# OLD_Trigger_And_Clock_Muxing.net
KiCad netlist of a schematic drawn in Altium Designer
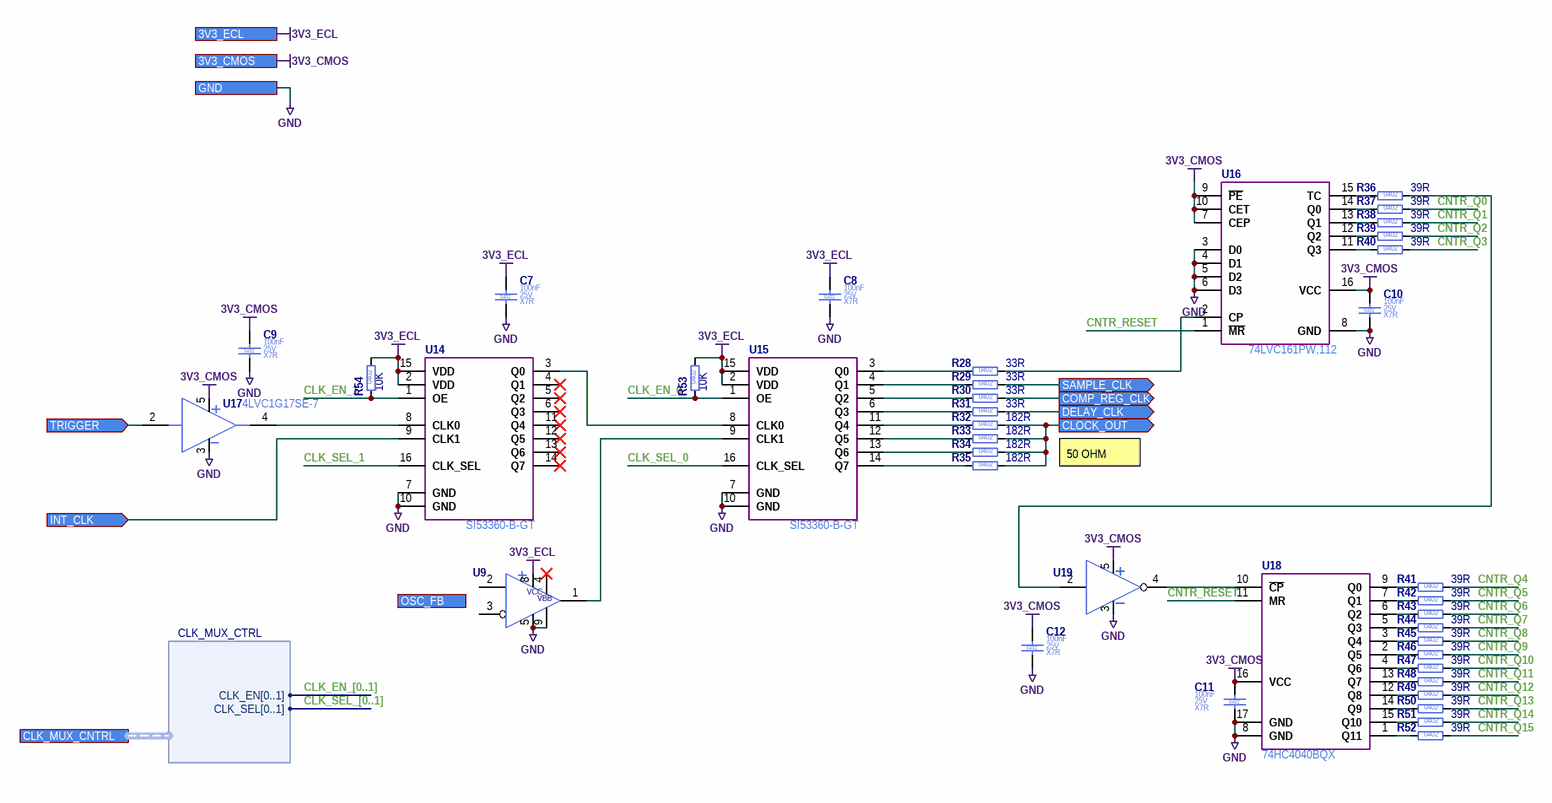
[diagram p0: OLD_Trigger_And_Clock_Muxing.SchDoc]

(export (version "E")
  (design (tool "Eeschema 10.0.6"))
  (components
    (comp (ref "C7")
      (value "C_100NF_25V_X7R_0402_10")
      (footprint "C_0402_1005")
      (description "Ceramic Capacitor")
      (fields
        (field (name "CASE/PACKAGE") "0402")
        (field (name "VOLTAGE RATING (DC)") "25V")
        (field (name "DIELECTRIC") "X7R")
        (field (name "CAPACITANCE") "100nF")
        (field (name "TOLERANCE") "10%")
        (field (name "MANUFACTURER PART NUMBER") "EMK105B7104KV-F")
      )
      (libsource (lib "7Sigma") (part "C"))
    )
    (comp (ref "C8")
      (value "C_100NF_25V_X7R_0402_10")
      (footprint "C_0402_1005")
      (description "Ceramic Capacitor")
      (fields
        (field (name "CASE/PACKAGE") "0402")
        (field (name "VOLTAGE RATING (DC)") "25V")
        (field (name "DIELECTRIC") "X7R")
        (field (name "CAPACITANCE") "100nF")
        (field (name "TOLERANCE") "10%")
        (field (name "MANUFACTURER PART NUMBER") "EMK105B7104KV-F")
      )
      (libsource (lib "7Sigma") (part "C"))
    )
    (comp (ref "C9")
      (value "C_100NF_25V_X7R_0402_10")
      (footprint "C_0402_1005")
      (description "Ceramic Capacitor")
      (fields
        (field (name "CASE/PACKAGE") "0402")
        (field (name "VOLTAGE RATING (DC)") "25V")
        (field (name "DIELECTRIC") "X7R")
        (field (name "CAPACITANCE") "100nF")
        (field (name "TOLERANCE") "10%")
        (field (name "MANUFACTURER PART NUMBER") "EMK105B7104KV-F")
      )
      (libsource (lib "7Sigma") (part "C"))
    )
    (comp (ref "C10")
      (value "C_100NF_25V_X7R_0402_10")
      (footprint "C_0402_1005")
      (description "Ceramic Capacitor")
      (fields
        (field (name "CASE/PACKAGE") "0402")
        (field (name "VOLTAGE RATING (DC)") "25V")
        (field (name "DIELECTRIC") "X7R")
        (field (name "CAPACITANCE") "100nF")
        (field (name "TOLERANCE") "10%")
        (field (name "MANUFACTURER PART NUMBER") "EMK105B7104KV-F")
      )
      (libsource (lib "7Sigma") (part "C"))
    )
    (comp (ref "C11")
      (value "C_100NF_25V_X7R_0402_10")
      (footprint "C_0402_1005")
      (description "Ceramic Capacitor")
      (fields
        (field (name "CASE/PACKAGE") "0402")
        (field (name "VOLTAGE RATING (DC)") "25V")
        (field (name "DIELECTRIC") "X7R")
        (field (name "CAPACITANCE") "100nF")
        (field (name "TOLERANCE") "10%")
        (field (name "MANUFACTURER PART NUMBER") "EMK105B7104KV-F")
      )
      (libsource (lib "7Sigma") (part "C"))
    )
    (comp (ref "C12")
      (value "C_100NF_25V_X7R_0402_10")
      (footprint "C_0402_1005")
      (description "Ceramic Capacitor")
      (fields
        (field (name "CASE/PACKAGE") "0402")
        (field (name "VOLTAGE RATING (DC)") "25V")
        (field (name "DIELECTRIC") "X7R")
        (field (name "CAPACITANCE") "100nF")
        (field (name "TOLERANCE") "10%")
        (field (name "MANUFACTURER PART NUMBER") "EMK105B7104KV-F")
      )
      (libsource (lib "7Sigma") (part "C"))
    )
    (comp (ref "R28")
      (value "R_33R_0402_1")
      (footprint "R_0402_1005")
      (description "Thick Film Resistor")
      (fields
        (field (name "RESISTANCE") "33R")
        (field (name "CASE/PACKAGE") "0402")
        (field (name "TOLERANCE") "1%")
        (field (name "MANUFACTURER") "Yageo")
      )
      (libsource (lib "7Sigma") (part "R"))
    )
    (comp (ref "R29")
      (value "R_33R_0402_1")
      (footprint "R_0402_1005")
      (description "Thick Film Resistor")
      (fields
        (field (name "RESISTANCE") "33R")
        (field (name "CASE/PACKAGE") "0402")
        (field (name "TOLERANCE") "1%")
        (field (name "MANUFACTURER") "Yageo")
      )
      (libsource (lib "7Sigma") (part "R"))
    )
    (comp (ref "R30")
      (value "R_33R_0402_1")
      (footprint "R_0402_1005")
      (description "Thick Film Resistor")
      (fields
        (field (name "RESISTANCE") "33R")
        (field (name "CASE/PACKAGE") "0402")
        (field (name "TOLERANCE") "1%")
        (field (name "MANUFACTURER") "Yageo")
      )
      (libsource (lib "7Sigma") (part "R"))
    )
    (comp (ref "R31")
      (value "R_33R_0402_1")
      (footprint "R_0402_1005")
      (description "Thick Film Resistor")
      (fields
        (field (name "RESISTANCE") "33R")
        (field (name "CASE/PACKAGE") "0402")
        (field (name "TOLERANCE") "1%")
        (field (name "MANUFACTURER") "Yageo")
      )
      (libsource (lib "7Sigma") (part "R"))
    )
    (comp (ref "R32")
      (value "R_182R_0402_1")
      (footprint "R_0402_1005")
      (description "Thick Film Resistor")
      (fields
        (field (name "RESISTANCE") "182R")
        (field (name "CASE/PACKAGE") "0402")
        (field (name "TOLERANCE") "1%")
        (field (name "MANUFACTURER") "Yageo")
      )
      (libsource (lib "7Sigma") (part "R"))
    )
    (comp (ref "R33")
      (value "R_182R_0402_1")
      (footprint "R_0402_1005")
      (description "Thick Film Resistor")
      (fields
        (field (name "RESISTANCE") "182R")
        (field (name "CASE/PACKAGE") "0402")
        (field (name "TOLERANCE") "1%")
        (field (name "MANUFACTURER") "Yageo")
      )
      (libsource (lib "7Sigma") (part "R"))
    )
    (comp (ref "R34")
      (value "R_182R_0402_1")
      (footprint "R_0402_1005")
      (description "Thick Film Resistor")
      (fields
        (field (name "RESISTANCE") "182R")
        (field (name "CASE/PACKAGE") "0402")
        (field (name "TOLERANCE") "1%")
        (field (name "MANUFACTURER") "Yageo")
      )
      (libsource (lib "7Sigma") (part "R"))
    )
    (comp (ref "R35")
      (value "R_182R_0402_1")
      (footprint "R_0402_1005")
      (description "Thick Film Resistor")
      (fields
        (field (name "RESISTANCE") "182R")
        (field (name "CASE/PACKAGE") "0402")
        (field (name "TOLERANCE") "1%")
        (field (name "MANUFACTURER") "Yageo")
      )
      (libsource (lib "7Sigma") (part "R"))
    )
    (comp (ref "R36")
      (value "R_39R_0402_1")
      (footprint "R_0402_1005")
      (description "Thick Film Resistor")
      (fields
        (field (name "RESISTANCE") "39R")
        (field (name "CASE/PACKAGE") "0402")
        (field (name "TOLERANCE") "1%")
        (field (name "MANUFACTURER") "Yageo")
      )
      (libsource (lib "7Sigma") (part "R"))
    )
    (comp (ref "R37")
      (value "R_39R_0402_1")
      (footprint "R_0402_1005")
      (description "Thick Film Resistor")
      (fields
        (field (name "RESISTANCE") "39R")
        (field (name "CASE/PACKAGE") "0402")
        (field (name "TOLERANCE") "1%")
        (field (name "MANUFACTURER") "Yageo")
      )
      (libsource (lib "7Sigma") (part "R"))
    )
    (comp (ref "R38")
      (value "R_39R_0402_1")
      (footprint "R_0402_1005")
      (description "Thick Film Resistor")
      (fields
        (field (name "RESISTANCE") "39R")
        (field (name "CASE/PACKAGE") "0402")
        (field (name "TOLERANCE") "1%")
        (field (name "MANUFACTURER") "Yageo")
      )
      (libsource (lib "7Sigma") (part "R"))
    )
    (comp (ref "R39")
      (value "R_39R_0402_1")
      (footprint "R_0402_1005")
      (description "Thick Film Resistor")
      (fields
        (field (name "RESISTANCE") "39R")
        (field (name "CASE/PACKAGE") "0402")
        (field (name "TOLERANCE") "1%")
        (field (name "MANUFACTURER") "Yageo")
      )
      (libsource (lib "7Sigma") (part "R"))
    )
    (comp (ref "R40")
      (value "R_39R_0402_1")
      (footprint "R_0402_1005")
      (description "Thick Film Resistor")
      (fields
        (field (name "RESISTANCE") "39R")
        (field (name "CASE/PACKAGE") "0402")
        (field (name "TOLERANCE") "1%")
        (field (name "MANUFACTURER") "Yageo")
      )
      (libsource (lib "7Sigma") (part "R"))
    )
    (comp (ref "R41")
      (value "R_39R_0402_1")
      (footprint "R_0402_1005")
      (description "Thick Film Resistor")
      (fields
        (field (name "RESISTANCE") "39R")
        (field (name "CASE/PACKAGE") "0402")
        (field (name "TOLERANCE") "1%")
        (field (name "MANUFACTURER") "Yageo")
      )
      (libsource (lib "7Sigma") (part "R"))
    )
    (comp (ref "R42")
      (value "R_39R_0402_1")
      (footprint "R_0402_1005")
      (description "Thick Film Resistor")
      (fields
        (field (name "RESISTANCE") "39R")
        (field (name "CASE/PACKAGE") "0402")
        (field (name "TOLERANCE") "1%")
        (field (name "MANUFACTURER") "Yageo")
      )
      (libsource (lib "7Sigma") (part "R"))
    )
    (comp (ref "R43")
      (value "R_39R_0402_1")
      (footprint "R_0402_1005")
      (description "Thick Film Resistor")
      (fields
        (field (name "RESISTANCE") "39R")
        (field (name "CASE/PACKAGE") "0402")
        (field (name "TOLERANCE") "1%")
        (field (name "MANUFACTURER") "Yageo")
      )
      (libsource (lib "7Sigma") (part "R"))
    )
    (comp (ref "R44")
      (value "R_39R_0402_1")
      (footprint "R_0402_1005")
      (description "Thick Film Resistor")
      (fields
        (field (name "RESISTANCE") "39R")
        (field (name "CASE/PACKAGE") "0402")
        (field (name "TOLERANCE") "1%")
        (field (name "MANUFACTURER") "Yageo")
      )
      (libsource (lib "7Sigma") (part "R"))
    )
    (comp (ref "R45")
      (value "R_39R_0402_1")
      (footprint "R_0402_1005")
      (description "Thick Film Resistor")
      (fields
        (field (name "RESISTANCE") "39R")
        (field (name "CASE/PACKAGE") "0402")
        (field (name "TOLERANCE") "1%")
        (field (name "MANUFACTURER") "Yageo")
      )
      (libsource (lib "7Sigma") (part "R"))
    )
    (comp (ref "R46")
      (value "R_39R_0402_1")
      (footprint "R_0402_1005")
      (description "Thick Film Resistor")
      (fields
        (field (name "RESISTANCE") "39R")
        (field (name "CASE/PACKAGE") "0402")
        (field (name "TOLERANCE") "1%")
        (field (name "MANUFACTURER") "Yageo")
      )
      (libsource (lib "7Sigma") (part "R"))
    )
    (comp (ref "R47")
      (value "R_39R_0402_1")
      (footprint "R_0402_1005")
      (description "Thick Film Resistor")
      (fields
        (field (name "RESISTANCE") "39R")
        (field (name "CASE/PACKAGE") "0402")
        (field (name "TOLERANCE") "1%")
        (field (name "MANUFACTURER") "Yageo")
      )
      (libsource (lib "7Sigma") (part "R"))
    )
    (comp (ref "R48")
      (value "R_39R_0402_1")
      (footprint "R_0402_1005")
      (description "Thick Film Resistor")
      (fields
        (field (name "RESISTANCE") "39R")
        (field (name "CASE/PACKAGE") "0402")
        (field (name "TOLERANCE") "1%")
        (field (name "MANUFACTURER") "Yageo")
      )
      (libsource (lib "7Sigma") (part "R"))
    )
    (comp (ref "R49")
      (value "R_39R_0402_1")
      (footprint "R_0402_1005")
      (description "Thick Film Resistor")
      (fields
        (field (name "RESISTANCE") "39R")
        (field (name "CASE/PACKAGE") "0402")
        (field (name "TOLERANCE") "1%")
        (field (name "MANUFACTURER") "Yageo")
      )
      (libsource (lib "7Sigma") (part "R"))
    )
    (comp (ref "R50")
      (value "R_39R_0402_1")
      (footprint "R_0402_1005")
      (description "Thick Film Resistor")
      (fields
        (field (name "RESISTANCE") "39R")
        (field (name "CASE/PACKAGE") "0402")
        (field (name "TOLERANCE") "1%")
        (field (name "MANUFACTURER") "Yageo")
      )
      (libsource (lib "7Sigma") (part "R"))
    )
    (comp (ref "R51")
      (value "R_39R_0402_1")
      (footprint "R_0402_1005")
      (description "Thick Film Resistor")
      (fields
        (field (name "RESISTANCE") "39R")
        (field (name "CASE/PACKAGE") "0402")
        (field (name "TOLERANCE") "1%")
        (field (name "MANUFACTURER") "Yageo")
      )
      (libsource (lib "7Sigma") (part "R"))
    )
    (comp (ref "R52")
      (value "R_39R_0402_1")
      (footprint "R_0402_1005")
      (description "Thick Film Resistor")
      (fields
        (field (name "RESISTANCE") "39R")
        (field (name "CASE/PACKAGE") "0402")
        (field (name "TOLERANCE") "1%")
        (field (name "MANUFACTURER") "Yageo")
      )
      (libsource (lib "7Sigma") (part "R"))
    )
    (comp (ref "R53")
      (value "R_10K_0402_1")
      (footprint "R_0402_1005")
      (description "Thick Film Resistor")
      (fields
        (field (name "RESISTANCE") "10K")
        (field (name "CASE/PACKAGE") "0402")
        (field (name "TOLERANCE") "1%")
        (field (name "MANUFACTURER") "Yageo")
      )
      (libsource (lib "7Sigma") (part "R"))
    )
    (comp (ref "R54")
      (value "R_10K_0402_1")
      (footprint "R_0402_1005")
      (description "Thick Film Resistor")
      (fields
        (field (name "RESISTANCE") "10K")
        (field (name "CASE/PACKAGE") "0402")
        (field (name "TOLERANCE") "1%")
        (field (name "MANUFACTURER") "Yageo")
      )
      (libsource (lib "7Sigma") (part "R"))
    )
    (comp (ref "U9")
      (value "MC100EPT21MNR4G")
      (footprint "SON50P200X80_HS-9N")
      (description "Differential LVPECL/LVDS/CML to LVTTL/LVCMOS Translator")
      (fields (field (name "MANUFACTURER") "ON Semiconductor"))
      (libsource (lib "7Sigma") (part "MC100EPT21"))
    )
    (comp (ref "U14")
      (value "Si53360-B-GT")
      (footprint "TSOP65P640X120-16N")
      (description "Low Jitter Clock Buffer")
      (fields
        (field (name "MANUFACTURER") "Silicon Labs")
        (field (name "MANUFACTURER PART NUMBER") "SI53360-B-GT")
      )
      (libsource (lib "7Sigma") (part "Si53360-B-GT"))
    )
    (comp (ref "U15")
      (value "Si53360-B-GT")
      (footprint "TSOP65P640X120-16N")
      (description "Low Jitter Clock Buffer")
      (fields
        (field (name "MANUFACTURER") "Silicon Labs")
        (field (name "MANUFACTURER PART NUMBER") "SI53360-B-GT")
      )
      (libsource (lib "7Sigma") (part "Si53360-B-GT"))
    )
    (comp (ref "U16")
      (value "74LVC161PW,112")
      (footprint "TSOP65P640X120-16N")
      (description "4 bit Counter with preset")
      (fields
        (field (name "MANUFACTURER") "Nexperia")
        (field (name "MANUFACTURER PART NUMBER") "74LVC161PW,112")
      )
      (libsource (lib "7Sigma") (part "74LVC161PW"))
    )
    (comp (ref "U17")
      (value "74LVC1G17SE-7")
      (footprint "SC70-5_SOT353_TSSOP5")
      (description "Schmitt Buffer")
      (fields
        (field (name "MANUFACTURER PART NUMBER") "74LVC1G17SE-7")
        (field (name "MANUFACTURER") "Diodes Incorporated")
      )
      (libsource (lib "7Sigma") (part "74LVC1G17SE-7"))
    )
    (comp (ref "U18")
      (value "74HC4040BQX")
      (footprint "QFN50P350X250X100_HS-17N")
      (description "12 bit binary ripple counter")
      (fields
        (field (name "MANUFACTURER PART NUMBER") "74HC4040BQX")
        (field (name "MANUFACTURER") "Nexperia")
      )
      (libsource (lib "7Sigma") (part "74HC4040BQX"))
    )
    (comp (ref "U19")
      (value "SN74AHC1G04DBVR")
      (footprint "SOT23-5_SC74A_SOT753_M")
      (description "Inverters Single")
      (fields (field (name "MANUFACTURER") "Texas Instruments"))
      (libsource (lib "7Sigma") (part "SN74AHC1G04DBVR"))
    )
  )
  (nets
    (net (code "2") (name "/CLK_EN_0") (class "Default")
      (node (ref "R53") (pin "1") (pinfunction "1_1") (pintype "passive"))
      (node (ref "U15") (pin "1") (pinfunction "OE_1") (pintype "passive"))
    )
    (net (code "3") (name "/CLK_EN_1") (class "Default")
      (node (ref "R54") (pin "1") (pinfunction "1_1") (pintype "passive"))
      (node (ref "U14") (pin "1") (pinfunction "OE_1") (pintype "passive"))
    )
    (net (code "5") (name "/CLK_SEL_0") (class "Default")
      (node (ref "U15") (pin "16") (pinfunction "CLK_SEL_16") (pintype "passive"))
    )
    (net (code "6") (name "/CLK_SEL_1") (class "Default")
      (node (ref "U14") (pin "16") (pinfunction "CLK_SEL_16") (pintype "passive"))
    )
    (net (code "8") (name "/CLOCK_OUT") (class "Default")
      (node (ref "R32") (pin "2") (pinfunction "2_2") (pintype "passive"))
      (node (ref "R33") (pin "2") (pinfunction "2_2") (pintype "passive"))
      (node (ref "R34") (pin "2") (pinfunction "2_2") (pintype "passive"))
      (node (ref "R35") (pin "2") (pinfunction "2_2") (pintype "passive"))
    )
    (net (code "9") (name "/CNTR_Q0") (class "Default")
      (node (ref "R37") (pin "2") (pinfunction "2_2") (pintype "passive"))
    )
    (net (code "10") (name "/CNTR_Q1") (class "Default")
      (node (ref "R38") (pin "2") (pinfunction "2_2") (pintype "passive"))
    )
    (net (code "11") (name "/CNTR_Q2") (class "Default")
      (node (ref "R39") (pin "2") (pinfunction "2_2") (pintype "passive"))
    )
    (net (code "12") (name "/CNTR_Q3") (class "Default")
      (node (ref "R40") (pin "2") (pinfunction "2_2") (pintype "passive"))
    )
    (net (code "13") (name "/CNTR_Q4") (class "Default")
      (node (ref "R41") (pin "2") (pinfunction "2_2") (pintype "passive"))
    )
    (net (code "14") (name "/CNTR_Q5") (class "Default")
      (node (ref "R42") (pin "2") (pinfunction "2_2") (pintype "passive"))
    )
    (net (code "15") (name "/CNTR_Q6") (class "Default")
      (node (ref "R43") (pin "2") (pinfunction "2_2") (pintype "passive"))
    )
    (net (code "16") (name "/CNTR_Q7") (class "Default")
      (node (ref "R44") (pin "2") (pinfunction "2_2") (pintype "passive"))
    )
    (net (code "17") (name "/CNTR_Q8") (class "Default")
      (node (ref "R45") (pin "2") (pinfunction "2_2") (pintype "passive"))
    )
    (net (code "18") (name "/CNTR_Q9") (class "Default")
      (node (ref "R46") (pin "2") (pinfunction "2_2") (pintype "passive"))
    )
    (net (code "19") (name "/CNTR_Q10") (class "Default")
      (node (ref "R47") (pin "2") (pinfunction "2_2") (pintype "passive"))
    )
    (net (code "20") (name "/CNTR_Q11") (class "Default")
      (node (ref "R48") (pin "2") (pinfunction "2_2") (pintype "passive"))
    )
    (net (code "21") (name "/CNTR_Q12") (class "Default")
      (node (ref "R49") (pin "2") (pinfunction "2_2") (pintype "passive"))
    )
    (net (code "22") (name "/CNTR_Q13") (class "Default")
      (node (ref "R50") (pin "2") (pinfunction "2_2") (pintype "passive"))
    )
    (net (code "23") (name "/CNTR_Q14") (class "Default")
      (node (ref "R51") (pin "2") (pinfunction "2_2") (pintype "passive"))
    )
    (net (code "24") (name "/CNTR_Q15") (class "Default")
      (node (ref "R52") (pin "2") (pinfunction "2_2") (pintype "passive"))
    )
    (net (code "25") (name "/CNTR_RESET") (class "Default")
      (node (ref "U16") (pin "1") (pinfunction "MR_1") (pintype "passive"))
      (node (ref "U18") (pin "11") (pinfunction "MR_11") (pintype "passive"))
    )
    (net (code "26") (name "/COMP_REG_CLK") (class "Default")
      (node (ref "R30") (pin "2") (pinfunction "2_2") (pintype "passive"))
    )
    (net (code "27") (name "/DELAY_CLK") (class "Default")
      (node (ref "R31") (pin "2") (pinfunction "2_2") (pintype "passive"))
    )
    (net (code "28") (name "/INT_CLK") (class "Default")
      (node (ref "U14") (pin "9") (pinfunction "CLK1_9") (pintype "passive"))
    )
    (net (code "30") (name "/SAMPLE_CLK") (class "Default")
      (node (ref "R29") (pin "2") (pinfunction "2_2") (pintype "passive"))
    )
    (net (code "31") (name "/TRIGGER") (class "Default")
      (node (ref "U17") (pin "2") (pinfunction "A_2") (pintype "passive"))
    )
    (net (code "33") (name "3V3_CMOS") (class "Default")
      (node (ref "C10") (pin "1") (pinfunction "1_1") (pintype "passive"))
      (node (ref "C11") (pin "1") (pinfunction "1_1") (pintype "passive"))
      (node (ref "C12") (pin "1") (pinfunction "1_1") (pintype "passive"))
      (node (ref "C9") (pin "1") (pinfunction "1_1") (pintype "passive"))
      (node (ref "U16") (pin "10") (pinfunction "CET_10") (pintype "passive"))
      (node (ref "U16") (pin "16") (pinfunction "VCC_16") (pintype "passive"))
      (node (ref "U16") (pin "7") (pinfunction "CEP_7") (pintype "passive"))
      (node (ref "U16") (pin "9") (pinfunction "PE_9") (pintype "passive"))
      (node (ref "U17") (pin "5") (pinfunction "VCC_5") (pintype "passive"))
      (node (ref "U18") (pin "16") (pinfunction "VCC_16") (pintype "passive"))
      (node (ref "U19") (pin "5") (pinfunction "VCC_5") (pintype "passive"))
    )
    (net (code "34") (name "3V3_ECL") (class "Default")
      (node (ref "C7") (pin "1") (pinfunction "1_1") (pintype "passive"))
      (node (ref "C8") (pin "1") (pinfunction "1_1") (pintype "passive"))
      (node (ref "R53") (pin "2") (pinfunction "2_2") (pintype "passive"))
      (node (ref "R54") (pin "2") (pinfunction "2_2") (pintype "passive"))
      (node (ref "U14") (pin "15") (pinfunction "VDD_15") (pintype "passive"))
      (node (ref "U14") (pin "2") (pinfunction "VDD_2") (pintype "passive"))
      (node (ref "U15") (pin "15") (pinfunction "VDD_15") (pintype "passive"))
      (node (ref "U15") (pin "2") (pinfunction "VDD_2") (pintype "passive"))
      (node (ref "U9") (pin "8") (pinfunction "VDD_8") (pintype "power_in"))
    )
    (net (code "35") (name "GND") (class "Default")
      (node (ref "C10") (pin "2") (pinfunction "2_2") (pintype "passive"))
      (node (ref "C11") (pin "2") (pinfunction "2_2") (pintype "passive"))
      (node (ref "C12") (pin "2") (pinfunction "2_2") (pintype "passive"))
      (node (ref "C7") (pin "2") (pinfunction "2_2") (pintype "passive"))
      (node (ref "C8") (pin "2") (pinfunction "2_2") (pintype "passive"))
      (node (ref "C9") (pin "2") (pinfunction "2_2") (pintype "passive"))
      (node (ref "U14") (pin "10") (pinfunction "GND_10") (pintype "passive"))
      (node (ref "U14") (pin "7") (pinfunction "GND_7") (pintype "passive"))
      (node (ref "U15") (pin "10") (pinfunction "GND_10") (pintype "passive"))
      (node (ref "U15") (pin "7") (pinfunction "GND_7") (pintype "passive"))
      (node (ref "U16") (pin "3") (pinfunction "D0_3") (pintype "passive"))
      (node (ref "U16") (pin "4") (pinfunction "D1_4") (pintype "passive"))
      (node (ref "U16") (pin "5") (pinfunction "D2_5") (pintype "passive"))
      (node (ref "U16") (pin "6") (pinfunction "D3_6") (pintype "passive"))
      (node (ref "U16") (pin "8") (pinfunction "GND_8") (pintype "passive"))
      (node (ref "U17") (pin "3") (pinfunction "GND_3") (pintype "passive"))
      (node (ref "U18") (pin "17") (pinfunction "GND_17") (pintype "passive"))
      (node (ref "U18") (pin "8") (pinfunction "GND_8") (pintype "passive"))
      (node (ref "U19") (pin "3") (pinfunction "GND_3") (pintype "passive"))
      (node (ref "U9") (pin "5") (pinfunction "VSS_5") (pintype "power_in"))
      (node (ref "U9") (pin "9") (pinfunction "VSS_9") (pintype "power_in"))
    )
    (net (code "36") (name "Net-(R36-Pad2)") (class "Default")
      (node (ref "R36") (pin "2") (pinfunction "2_2") (pintype "passive"))
      (node (ref "U19") (pin "2") (pinfunction "2_2") (pintype "passive"))
    )
    (net (code "37") (name "Net-(U14-CLK0)") (class "Default")
      (node (ref "U14") (pin "8") (pinfunction "CLK0_8") (pintype "passive"))
      (node (ref "U17") (pin "4") (pinfunction "Y_4") (pintype "passive"))
    )
    (net (code "38") (name "Net-(U14-Q0)") (class "Default")
      (node (ref "U14") (pin "3") (pinfunction "Q0_3") (pintype "passive"))
      (node (ref "U15") (pin "8") (pinfunction "CLK0_8") (pintype "passive"))
    )
    (net (code "39") (name "Net-(U15-CLK1)") (class "Default")
      (node (ref "U15") (pin "9") (pinfunction "CLK1_9") (pintype "passive"))
      (node (ref "U9") (pin "1") (pinfunction "OUTA_1") (pintype "passive"))
    )
    (net (code "40") (name "Net-(U15-Q0)") (class "Default")
      (node (ref "R28") (pin "1") (pinfunction "1_1") (pintype "passive"))
      (node (ref "U15") (pin "3") (pinfunction "Q0_3") (pintype "passive"))
    )
    (net (code "41") (name "Net-(U15-Q1)") (class "Default")
      (node (ref "R29") (pin "1") (pinfunction "1_1") (pintype "passive"))
      (node (ref "U15") (pin "4") (pinfunction "Q1_4") (pintype "passive"))
    )
    (net (code "42") (name "Net-(U15-Q2)") (class "Default")
      (node (ref "R30") (pin "1") (pinfunction "1_1") (pintype "passive"))
      (node (ref "U15") (pin "5") (pinfunction "Q2_5") (pintype "passive"))
    )
    (net (code "43") (name "Net-(U15-Q3)") (class "Default")
      (node (ref "R31") (pin "1") (pinfunction "1_1") (pintype "passive"))
      (node (ref "U15") (pin "6") (pinfunction "Q3_6") (pintype "passive"))
    )
    (net (code "44") (name "Net-(U15-Q4)") (class "Default")
      (node (ref "R32") (pin "1") (pinfunction "1_1") (pintype "passive"))
      (node (ref "U15") (pin "11") (pinfunction "Q4_11") (pintype "passive"))
    )
    (net (code "45") (name "Net-(U15-Q5)") (class "Default")
      (node (ref "R33") (pin "1") (pinfunction "1_1") (pintype "passive"))
      (node (ref "U15") (pin "12") (pinfunction "Q5_12") (pintype "passive"))
    )
    (net (code "46") (name "Net-(U15-Q6)") (class "Default")
      (node (ref "R34") (pin "1") (pinfunction "1_1") (pintype "passive"))
      (node (ref "U15") (pin "13") (pinfunction "Q6_13") (pintype "passive"))
    )
    (net (code "47") (name "Net-(U15-Q7)") (class "Default")
      (node (ref "R35") (pin "1") (pinfunction "1_1") (pintype "passive"))
      (node (ref "U15") (pin "14") (pinfunction "Q7_14") (pintype "passive"))
    )
    (net (code "48") (name "Net-(U16-CP)") (class "Default")
      (node (ref "R28") (pin "2") (pinfunction "2_2") (pintype "passive"))
      (node (ref "U16") (pin "2") (pinfunction "CP_2") (pintype "passive"))
    )
    (net (code "49") (name "Net-(U16-Q0)") (class "Default")
      (node (ref "R37") (pin "1") (pinfunction "1_1") (pintype "passive"))
      (node (ref "U16") (pin "14") (pinfunction "Q0_14") (pintype "passive"))
    )
    (net (code "50") (name "Net-(U16-Q1)") (class "Default")
      (node (ref "R38") (pin "1") (pinfunction "1_1") (pintype "passive"))
      (node (ref "U16") (pin "13") (pinfunction "Q1_13") (pintype "passive"))
    )
    (net (code "51") (name "Net-(U16-Q2)") (class "Default")
      (node (ref "R39") (pin "1") (pinfunction "1_1") (pintype "passive"))
      (node (ref "U16") (pin "12") (pinfunction "Q2_12") (pintype "passive"))
    )
    (net (code "52") (name "Net-(U16-Q3)") (class "Default")
      (node (ref "R40") (pin "1") (pinfunction "1_1") (pintype "passive"))
      (node (ref "U16") (pin "11") (pinfunction "Q3_11") (pintype "passive"))
    )
    (net (code "53") (name "Net-(U16-TC)") (class "Default")
      (node (ref "R36") (pin "1") (pinfunction "1_1") (pintype "passive"))
      (node (ref "U16") (pin "15") (pinfunction "TC_15") (pintype "passive"))
    )
    (net (code "54") (name "Net-(U18-CP)") (class "Default")
      (node (ref "U18") (pin "10") (pinfunction "CP_10") (pintype "passive"))
      (node (ref "U19") (pin "4") (pinfunction "OutY_4") (pintype "passive"))
    )
    (net (code "55") (name "Net-(U18-Q0)") (class "Default")
      (node (ref "R41") (pin "1") (pinfunction "1_1") (pintype "passive"))
      (node (ref "U18") (pin "9") (pinfunction "Q0_9") (pintype "passive"))
    )
    (net (code "56") (name "Net-(U18-Q1)") (class "Default")
      (node (ref "R42") (pin "1") (pinfunction "1_1") (pintype "passive"))
      (node (ref "U18") (pin "7") (pinfunction "Q1_7") (pintype "passive"))
    )
    (net (code "57") (name "Net-(U18-Q2)") (class "Default")
      (node (ref "R43") (pin "1") (pinfunction "1_1") (pintype "passive"))
      (node (ref "U18") (pin "6") (pinfunction "Q2_6") (pintype "passive"))
    )
    (net (code "58") (name "Net-(U18-Q3)") (class "Default")
      (node (ref "R44") (pin "1") (pinfunction "1_1") (pintype "passive"))
      (node (ref "U18") (pin "5") (pinfunction "Q3_5") (pintype "passive"))
    )
    (net (code "59") (name "Net-(U18-Q4)_1") (class "Default")
      (node (ref "R45") (pin "1") (pinfunction "1_1") (pintype "passive"))
      (node (ref "U18") (pin "3") (pinfunction "Q4_3") (pintype "passive"))
    )
    (net (code "60") (name "Net-(U18-Q5)") (class "Default")
      (node (ref "R46") (pin "1") (pinfunction "1_1") (pintype "passive"))
      (node (ref "U18") (pin "2") (pinfunction "Q5_2") (pintype "passive"))
    )
    (net (code "61") (name "Net-(U18-Q6)") (class "Default")
      (node (ref "R47") (pin "1") (pinfunction "1_1") (pintype "passive"))
      (node (ref "U18") (pin "4") (pinfunction "Q6_4") (pintype "passive"))
    )
    (net (code "62") (name "Net-(U18-Q7)") (class "Default")
      (node (ref "R48") (pin "1") (pinfunction "1_1") (pintype "passive"))
      (node (ref "U18") (pin "13") (pinfunction "Q7_13") (pintype "passive"))
    )
    (net (code "63") (name "Net-(U18-Q8)") (class "Default")
      (node (ref "R49") (pin "1") (pinfunction "1_1") (pintype "passive"))
      (node (ref "U18") (pin "12") (pinfunction "Q8_12") (pintype "passive"))
    )
    (net (code "64") (name "Net-(U18-Q9)") (class "Default")
      (node (ref "R50") (pin "1") (pinfunction "1_1") (pintype "passive"))
      (node (ref "U18") (pin "14") (pinfunction "Q9_14") (pintype "passive"))
    )
    (net (code "65") (name "Net-(U18-Q10)") (class "Default")
      (node (ref "R51") (pin "1") (pinfunction "1_1") (pintype "passive"))
      (node (ref "U18") (pin "15") (pinfunction "Q10_15") (pintype "passive"))
    )
    (net (code "66") (name "Net-(U18-Q11)") (class "Default")
      (node (ref "R52") (pin "1") (pinfunction "1_1") (pintype "passive"))
      (node (ref "U18") (pin "1") (pinfunction "Q11_1") (pintype "passive"))
    )
    (net (code "67") (name "unconnected-(U9-D-Pad2)") (class "Default")
      (node (ref "U9") (pin "2") (pinfunction "D_2") (pintype "passive"))
    )
    (net (code "68") (name "unconnected-(U9-D-Pad3)") (class "Default")
      (node (ref "U9") (pin "3") (pinfunction "D_3") (pintype "passive"))
    )
    (net (code "69") (name "unconnected-(U9-VDD-Pad4)") (class "Default")
      (node (ref "U9") (pin "4") (pinfunction "VDD_4") (pintype "power_in+no_connect"))
    )
    (net (code "70") (name "unconnected-(U14-Q1-Pad4)") (class "Default")
      (node (ref "U14") (pin "4") (pinfunction "Q1_4") (pintype "passive+no_connect"))
    )
    (net (code "71") (name "unconnected-(U14-Q2-Pad5)") (class "Default")
      (node (ref "U14") (pin "5") (pinfunction "Q2_5") (pintype "passive+no_connect"))
    )
    (net (code "72") (name "unconnected-(U14-Q3-Pad6)") (class "Default")
      (node (ref "U14") (pin "6") (pinfunction "Q3_6") (pintype "passive+no_connect"))
    )
    (net (code "73") (name "unconnected-(U14-Q4-Pad11)") (class "Default")
      (node (ref "U14") (pin "11") (pinfunction "Q4_11") (pintype "passive+no_connect"))
    )
    (net (code "74") (name "unconnected-(U14-Q5-Pad12)") (class "Default")
      (node (ref "U14") (pin "12") (pinfunction "Q5_12") (pintype "passive+no_connect"))
    )
    (net (code "75") (name "unconnected-(U14-Q6-Pad13)") (class "Default")
      (node (ref "U14") (pin "13") (pinfunction "Q6_13") (pintype "passive+no_connect"))
    )
    (net (code "76") (name "unconnected-(U14-Q7-Pad14)") (class "Default")
      (node (ref "U14") (pin "14") (pinfunction "Q7_14") (pintype "passive+no_connect"))
    )
    (net (code "77") (name "unconnected-(U18-Q4-Pad3)") (class "Default")
      (node (ref "U18") (pin "3") (pinfunction "Q4_3") (pintype "input"))
    )
    (net (code "78") (name "unconnected-(U19-NC-Pad1)") (class "Default")
      (node (ref "U19") (pin "1") (pinfunction "NC_1") (pintype "passive"))
    )
  )
)
